# FLUOLAMP_8W_DRIVER.net
KiCad netlist of a schematic drawn in Altium Designer
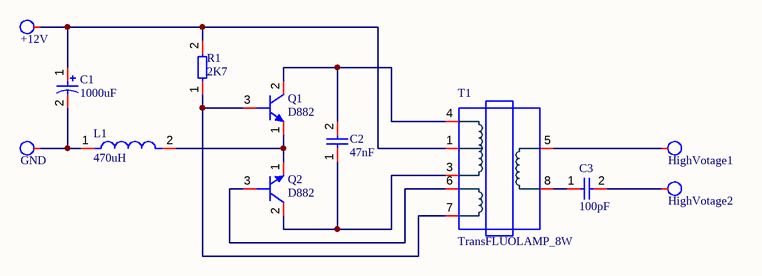
[diagram p0: FLUOLAMP_8W_DRIVER.SchDoc]

(export (version "E")
  (design (tool "Eeschema 10.0.6"))
  (components
    (comp (ref "+12V")
      (value "SolderPoint")
      (footprint "SolderPoint")
      (libsource (lib "Lib31082020") (part "SolderPoint"))
    )
    (comp (ref "C1")
      (value "1000uF")
      (footprint "CAP_RAD_7mm")
      (libsource (lib "Lib31082020") (part "Capacitor(Radian)"))
    )
    (comp (ref "C2")
      (value "47nF")
      (footprint "CAP_DISC_4x3_YL-LM")
      (libsource (lib "Lib31082020") (part "Capacitors(Disc)"))
    )
    (comp (ref "C3")
      (value "100pF")
      (footprint "CAP_DISC_9x3_BL")
      (libsource (lib "Lib31082020") (part "Capacitors(Disc)"))
    )
    (comp (ref "GND")
      (value "SolderPoint")
      (footprint "SolderPoint")
      (libsource (lib "Lib31082020") (part "SolderPoint"))
    )
    (comp (ref "HighVotage1")
      (value "SolderPoint")
      (footprint "SolderPoint")
      (libsource (lib "Lib31082020") (part "SolderPoint"))
    )
    (comp (ref "HighVotage2")
      (value "SolderPoint")
      (footprint "SolderPoint")
      (libsource (lib "Lib31082020") (part "SolderPoint"))
    )
    (comp (ref "L1")
      (value "470uH")
      (footprint "INDUCTOR_470uH")
      (libsource (lib "Lib31082020") (part "Inductor"))
    )
    (comp (ref "Q1")
      (value "D882")
      (footprint "TO-126")
      (libsource (lib "Lib31082020") (part "D882 (TO-126)"))
    )
    (comp (ref "Q2")
      (value "D882")
      (footprint "TO-126")
      (libsource (lib "Lib31082020") (part "D882 (TO-126)"))
    )
    (comp (ref "R1")
      (value "2K7")
      (footprint "RES-0.25W-H-MF")
      (libsource (lib "Lib31082020") (part "Resistors THD"))
    )
    (comp (ref "T1")
      (value "TransFLUOLAMP_8W")
      (footprint "TRANS_FLUOLAMP_8W")
      (libsource (lib "Lib31082020") (part "TransFLUOLAMP_8W"))
    )
  )
  (nets
    (net (code "1") (name "Net-(+12V-Pad1)") (class "Default")
      (node (ref "+12V") (pin "1") (pinfunction "1_1") (pintype "passive"))
      (node (ref "C1") (pin "1") (pinfunction "1_1") (pintype "passive"))
      (node (ref "R1") (pin "2") (pinfunction "2_2") (pintype "passive"))
      (node (ref "T1") (pin "1") (pinfunction "1_1") (pintype "passive"))
    )
    (net (code "2") (name "Net-(C1-Pad2)") (class "Default")
      (node (ref "C1") (pin "2") (pinfunction "2_2") (pintype "passive"))
      (node (ref "GND") (pin "1") (pinfunction "1_1") (pintype "passive"))
      (node (ref "L1") (pin "1") (pinfunction "1_1") (pintype "passive"))
    )
    (net (code "3") (name "Net-(C3-Pad1)") (class "Default")
      (node (ref "C3") (pin "1") (pinfunction "1_1") (pintype "passive"))
      (node (ref "T1") (pin "8") (pinfunction "8_8") (pintype "passive"))
    )
    (net (code "4") (name "Net-(C3-Pad2)") (class "Default")
      (node (ref "C3") (pin "2") (pinfunction "2_2") (pintype "passive"))
      (node (ref "HighVotage2") (pin "1") (pinfunction "1_1") (pintype "passive"))
    )
    (net (code "5") (name "Net-(HighVotage1-Pad1)") (class "Default")
      (node (ref "HighVotage1") (pin "1") (pinfunction "1_1") (pintype "passive"))
      (node (ref "T1") (pin "5") (pinfunction "5_5") (pintype "passive"))
    )
    (net (code "6") (name "Net-(Q1-B)") (class "Default")
      (node (ref "Q1") (pin "3") (pinfunction "B_3") (pintype "passive"))
      (node (ref "R1") (pin "1") (pinfunction "1_1") (pintype "passive"))
      (node (ref "T1") (pin "7") (pinfunction "7_7") (pintype "passive"))
    )
    (net (code "7") (name "Net-(Q1-C)") (class "Default")
      (node (ref "C2") (pin "2") (pinfunction "2_2") (pintype "passive"))
      (node (ref "Q1") (pin "2") (pinfunction "C_2") (pintype "passive"))
      (node (ref "T1") (pin "4") (pinfunction "4_4") (pintype "passive"))
    )
    (net (code "8") (name "Net-(Q1-E)") (class "Default")
      (node (ref "L1") (pin "2") (pinfunction "2_2") (pintype "passive"))
      (node (ref "Q1") (pin "1") (pinfunction "E_1") (pintype "passive"))
      (node (ref "Q2") (pin "1") (pinfunction "E_1") (pintype "passive"))
    )
    (net (code "9") (name "Net-(Q2-B)") (class "Default")
      (node (ref "Q2") (pin "3") (pinfunction "B_3") (pintype "passive"))
      (node (ref "T1") (pin "6") (pinfunction "6_6") (pintype "passive"))
    )
    (net (code "10") (name "Net-(Q2-C)") (class "Default")
      (node (ref "C2") (pin "1") (pinfunction "1_1") (pintype "passive"))
      (node (ref "Q2") (pin "2") (pinfunction "C_2") (pintype "passive"))
      (node (ref "T1") (pin "3") (pinfunction "3_3") (pintype "passive"))
    )
  )
)
